# 13_TYPEC0_PROG.net
KiCad netlist of a schematic drawn in Altium Designer
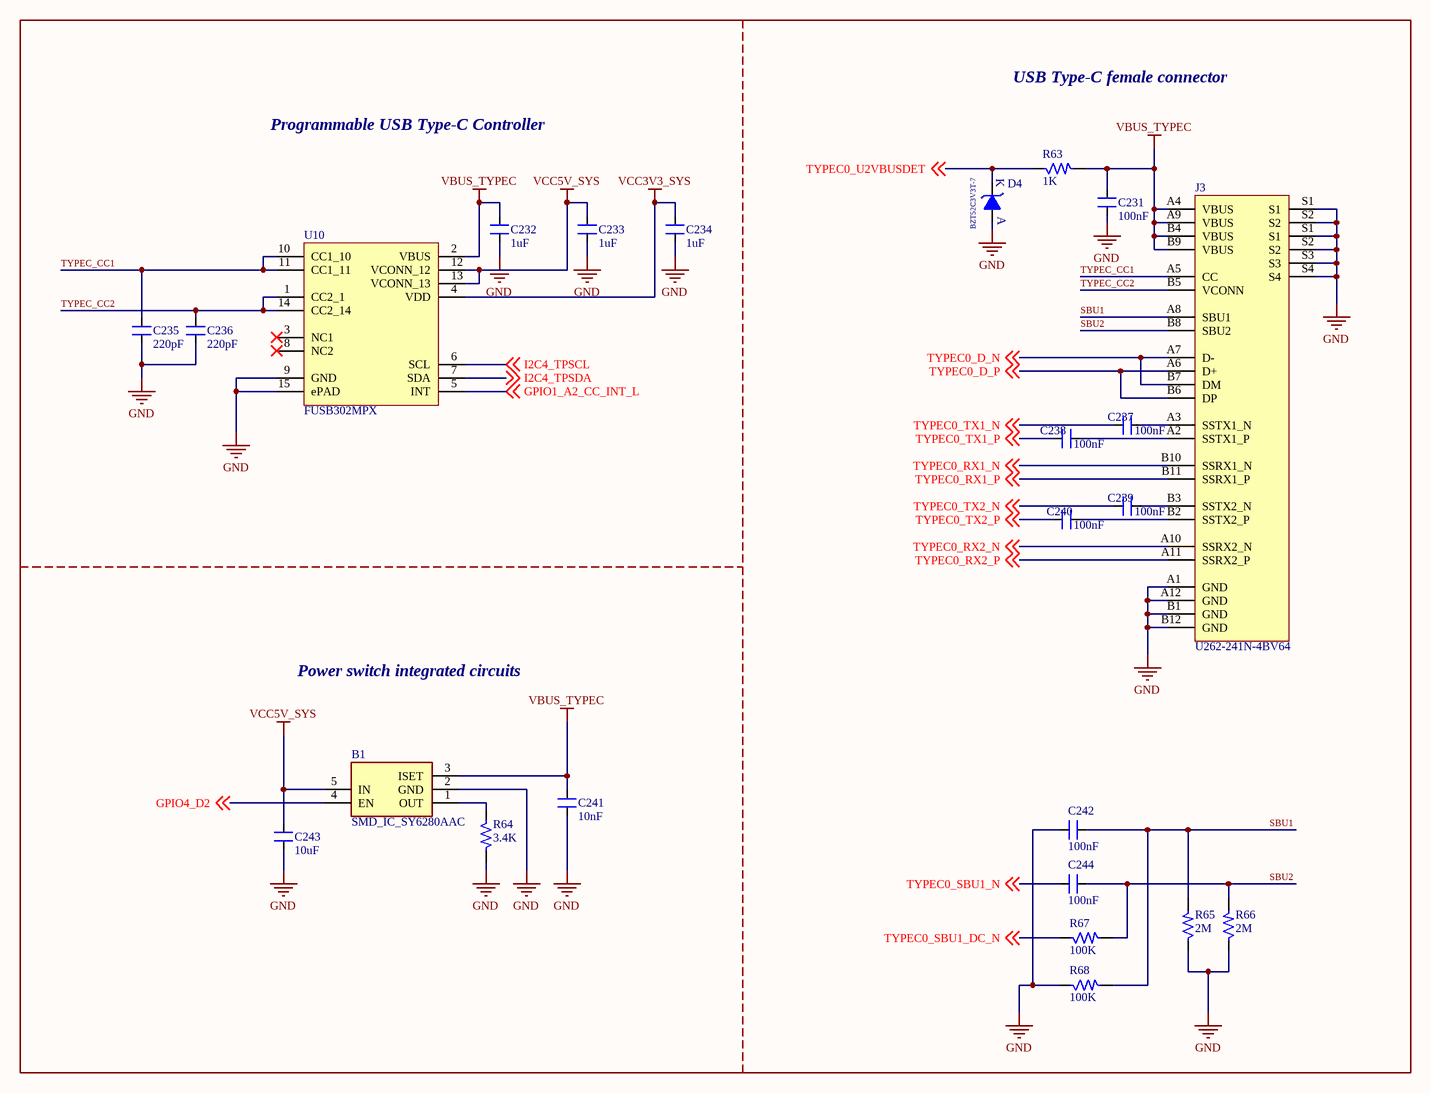
[diagram p0: [13] TYPEC0_PROG.SchDoc]

(export (version "E")
  (design (tool "Eeschema 10.0.6"))
  (components
    (comp (ref "B1")
      (value "SMD_IC_SY6280AAC")
      (footprint "SOT95P285X140-5N")
      (description "Power Switch ICs - Power Distribution")
      (fields
        (field (name "MOUSER PART NUMBER") "909-SMDICSY6280AAC")
        (field (name "MANUFACTURER_PART_NUMBER") "SMD IC SY6280AAC")
      )
      (libsource (lib "SMD_IC_SY6280AAC") (part "SMD_IC_SY6280AAC"))
    )
    (comp (ref "C231")
      (value "100nF")
      (footprint "CAP_0402")
      (description "0.1µF ±10% 25V Ceramic Capacitor X7R 0402 (1005 Metric)")
      (fields
        (field (name "MANUFACTURER") "Walsin Technology Corporation")
        (field (name "MANUFACTURER PART NUMBER") "0402B104K250CT")
      )
      (libsource (lib "EsteemPCB_SOM_Course_intlib") (part "CAP_100nF-25V-10%-0402"))
    )
    (comp (ref "C232")
      (value "1uF")
      (footprint "CAP_0402")
      (description "1µF ±10% 10V Ceramic Capacitor X6S 0402 (1005 Metric)")
      (fields
        (field (name "MANUFACTURER") "Murata Electronics")
        (field (name "MANUFACTURER PART NUMBER") "GRT155C81A105KE01D")
      )
      (libsource (lib "EsteemPCB_SOM_Course_intlib") (part "CAP_1uF-10V-10%-0402"))
    )
    (comp (ref "C233")
      (value "1uF")
      (footprint "CAP_0402")
      (description "1µF ±10% 10V Ceramic Capacitor X6S 0402 (1005 Metric)")
      (fields
        (field (name "MANUFACTURER") "Murata Electronics")
        (field (name "MANUFACTURER PART NUMBER") "GRT155C81A105KE01D")
      )
      (libsource (lib "EsteemPCB_SOM_Course_intlib") (part "CAP_1uF-10V-10%-0402"))
    )
    (comp (ref "C234")
      (value "1uF")
      (footprint "CAP_0402")
      (description "1µF ±10% 10V Ceramic Capacitor X6S 0402 (1005 Metric)")
      (fields
        (field (name "MANUFACTURER") "Murata Electronics")
        (field (name "MANUFACTURER PART NUMBER") "GRT155C81A105KE01D")
      )
      (libsource (lib "EsteemPCB_SOM_Course_intlib") (part "CAP_1uF-10V-10%-0402"))
    )
    (comp (ref "C235")
      (value "220pF")
      (footprint "CAP_0402")
      (description "220pF ±10% 10V Ceramic Capacitor X7R 0402 (1005 Metric)")
      (fields
        (field (name "MANUFACTURER") "KEMET")
        (field (name "MANUFACTURER PART NUMBER") "C0402C221K8RAC7867")
      )
      (libsource (lib "EsteemPCB_SOM_Course_intlib") (part "CAP_220pF-10V-10%-0402"))
    )
    (comp (ref "C236")
      (value "220pF")
      (footprint "CAP_0402")
      (description "220pF ±10% 10V Ceramic Capacitor X7R 0402 (1005 Metric)")
      (fields
        (field (name "MANUFACTURER") "KEMET")
        (field (name "MANUFACTURER PART NUMBER") "C0402C221K8RAC7867")
      )
      (libsource (lib "EsteemPCB_SOM_Course_intlib") (part "CAP_220pF-10V-10%-0402"))
    )
    (comp (ref "C237")
      (value "100nF")
      (footprint "CAP_0201")
      (description "0.1µF ±10% 25V Ceramic Capacitor X5R 0201 (0603 Metric)")
      (fields
        (field (name "MANUFACTURER") "TDK Corporation")
        (field (name "MANUFACTURER PART NUMBER") "C0603X5R1E104K030BB")
      )
      (libsource (lib "EsteemPCB_SOM_Course_intlib") (part "CAP_100nF-25V-10%-0201"))
    )
    (comp (ref "C238")
      (value "100nF")
      (footprint "CAP_0201")
      (description "0.1µF ±10% 25V Ceramic Capacitor X5R 0201 (0603 Metric)")
      (fields
        (field (name "MANUFACTURER") "TDK Corporation")
        (field (name "MANUFACTURER PART NUMBER") "C0603X5R1E104K030BB")
      )
      (libsource (lib "EsteemPCB_SOM_Course_intlib") (part "CAP_100nF-25V-10%-0201"))
    )
    (comp (ref "C239")
      (value "100nF")
      (footprint "CAP_0201")
      (description "0.1µF ±10% 25V Ceramic Capacitor X5R 0201 (0603 Metric)")
      (fields
        (field (name "MANUFACTURER") "TDK Corporation")
        (field (name "MANUFACTURER PART NUMBER") "C0603X5R1E104K030BB")
      )
      (libsource (lib "EsteemPCB_SOM_Course_intlib") (part "CAP_100nF-25V-10%-0201"))
    )
    (comp (ref "C240")
      (value "100nF")
      (footprint "CAP_0201")
      (description "0.1µF ±10% 25V Ceramic Capacitor X5R 0201 (0603 Metric)")
      (fields
        (field (name "MANUFACTURER") "TDK Corporation")
        (field (name "MANUFACTURER PART NUMBER") "C0603X5R1E104K030BB")
      )
      (libsource (lib "EsteemPCB_SOM_Course_intlib") (part "CAP_100nF-25V-10%-0201"))
    )
    (comp (ref "C241")
      (value "10nF")
      (footprint "CAP_0402")
      (description "10000pF ±10% 10V Ceramic Capacitor X7R 0402 (1005 Metric)")
      (fields
        (field (name "MANUFACTURER") "AVX Corporation")
        (field (name "MANUFACTURER PART NUMBER") "0402ZC103KAT2A")
      )
      (libsource (lib "EsteemPCB_SOM_Course_intlib") (part "CAP_10nF-10V-10%-0402"))
    )
    (comp (ref "C242")
      (value "100nF")
      (footprint "CAP_0201")
      (description "0.1µF ±10% 25V Ceramic Capacitor X5R 0201 (0603 Metric)")
      (fields
        (field (name "MANUFACTURER") "TDK Corporation")
        (field (name "MANUFACTURER PART NUMBER") "C0603X5R1E104K030BB")
      )
      (libsource (lib "EsteemPCB_SOM_Course_intlib") (part "CAP_100nF-25V-10%-0201"))
    )
    (comp (ref "C243")
      (value "10uF")
      (footprint "CAP_0402")
      (description "10µF ±20% 10V Ceramic Capacitor X5R 0402 (1005 Metric)")
      (fields
        (field (name "MANUFACTURER PART NUMBER") "CL05A106MP5NUNC")
        (field (name "MANUFACTURER") "Samsung Electro-Mechanics")
      )
      (libsource (lib "EsteemPCB_SOM_Course_intlib") (part "CAP_10uF-10V-20%-0402"))
    )
    (comp (ref "C244")
      (value "100nF")
      (footprint "CAP_0201")
      (description "0.1µF ±10% 25V Ceramic Capacitor X5R 0201 (0603 Metric)")
      (fields
        (field (name "MANUFACTURER") "TDK Corporation")
        (field (name "MANUFACTURER PART NUMBER") "C0603X5R1E104K030BB")
      )
      (libsource (lib "EsteemPCB_SOM_Course_intlib") (part "CAP_100nF-25V-10%-0201"))
    )
    (comp (ref "D4")
      (value "BZT52C3V3T-7")
      (footprint "DIO_SOD523")
      (description "Zener Diode 3.3V 300mW ±6% Surface Mount SOD-523")
      (fields (field (name "MANUFACTURER") "Diodes Incorporated"))
      (libsource (lib "EsteemPCB_SOM_Course_intlib") (part "DIO-Z_3.3V-300mW-SOD-523"))
    )
    (comp (ref "J3")
      (value "U262-241N-4BV64")
      (footprint "CON24_19.64_U262-241N-4BV64_TH_RA")
      (description "USB - Type C Female 24 SMD USB Connectors RoHS")
      (fields (field (name "MANUFACTURER") "XKB Connectivity"))
      (libsource (lib "EsteemPCB_SOM_Course_intlib") (part "CON-TYPEC_U262-241N-4BV64-SMD"))
    )
    (comp (ref "R63")
      (value "1K")
      (footprint "RES_0402")
      (description "1 kOhms ±1% 0.1W, 1/10W Chip Resistor 0402 (1005 Metric) Anti-Sulfur Thin Film")
      (fields
        (field (name "MANUFACTURER") "Vishay Beyschlag/Draloric/BC Components")
        (field (name "MANUFACTURER PART NUMBER") "MCS04020C1001FE000")
      )
      (libsource (lib "EsteemPCB_SOM_Course_intlib") (part "RES_1K-0.1W-1%-0402"))
    )
    (comp (ref "R64")
      (value "3.4K")
      (footprint "RES_0402")
      (description "3.4 kOhms ±1% 0.1W, 1/10W Chip Resistor 0402 (1005 Metric) Automotive AEC-Q200 Thick Film")
      (fields
        (field (name "MANUFACTURER") "Panasonic Electronic Components")
        (field (name "MANUFACTURER PART NUMBER") "ERJ-2RKF3401X")
      )
      (libsource (lib "EsteemPCB_SOM_Course_intlib") (part "RES_3.4K-0.1W-1%-0402"))
    )
    (comp (ref "R65")
      (value "2M")
      (footprint "RES_0201")
      (description "2 MOhms ±1% 0.05W, 1/20W Chip Resistor 0201 (0603 Metric) Thick Film")
      (fields
        (field (name "MANUFACTURER") "Yageo")
        (field (name "MANUFACTURER PART NUMBER") "RC0201FR-072ML")
      )
      (libsource (lib "EsteemPCB_SOM_Course_intlib") (part "RES_2M-0.05W-1%-0201"))
    )
    (comp (ref "R66")
      (value "2M")
      (footprint "RES_0201")
      (description "2 MOhms ±1% 0.05W, 1/20W Chip Resistor 0201 (0603 Metric) Thick Film")
      (fields
        (field (name "MANUFACTURER") "Yageo")
        (field (name "MANUFACTURER PART NUMBER") "RC0201FR-072ML")
      )
      (libsource (lib "EsteemPCB_SOM_Course_intlib") (part "RES_2M-0.05W-1%-0201"))
    )
    (comp (ref "R67")
      (value "100K")
      (footprint "RES_0201")
      (description "100 kOhms ±1% 0.05W, 1/20W Chip Resistor 0201 (0603 Metric) Automotive AEC-Q200 Thick Film")
      (fields
        (field (name "MANUFACTURER") "Panasonic Electronic Components")
        (field (name "MANUFACTURER PART NUMBER") "ERJ-1GNF1003C")
      )
      (libsource (lib "EsteemPCB_SOM_Course_intlib") (part "RES_100K-0.05W-1%-0201"))
    )
    (comp (ref "R68")
      (value "100K")
      (footprint "RES_0201")
      (description "100 kOhms ±1% 0.05W, 1/20W Chip Resistor 0201 (0603 Metric) Automotive AEC-Q200 Thick Film")
      (fields
        (field (name "MANUFACTURER") "Panasonic Electronic Components")
        (field (name "MANUFACTURER PART NUMBER") "ERJ-1GNF1003C")
      )
      (libsource (lib "EsteemPCB_SOM_Course_intlib") (part "RES_100K-0.05W-1%-0201"))
    )
    (comp (ref "U10")
      (value "FUSB302MPX")
      (footprint "MLP-14_98.4X98.4_SMD")
      (description "USB Controller USB 3.1 USB Interface 14-MLP (2.5x2.5)")
      (fields (field (name "MANUFACTURER") "ON Semiconductor"))
      (libsource (lib "EsteemPCB_SOM_Course_intlib") (part "IC_FUSB302MPX"))
    )
  )
  (nets
    (net (code "1") (name "/SBU1") (class "Default")
      (node (ref "C242") (pin "2") (pinfunction "2_2") (pintype "passive"))
      (node (ref "J3") (pin "A8") (pinfunction "SBU1_A8") (pintype "passive"))
      (node (ref "R65") (pin "2") (pinfunction "2_2") (pintype "passive"))
      (node (ref "R68") (pin "2") (pinfunction "2_2") (pintype "passive"))
    )
    (net (code "2") (name "/SBU2") (class "Default")
      (node (ref "C244") (pin "2") (pinfunction "2_2") (pintype "passive"))
      (node (ref "J3") (pin "B8") (pinfunction "SBU2_B8") (pintype "passive"))
      (node (ref "R66") (pin "2") (pinfunction "2_2") (pintype "passive"))
      (node (ref "R67") (pin "2") (pinfunction "2_2") (pintype "passive"))
    )
    (net (code "3") (name "/TYPEC_CC1") (class "Default")
      (node (ref "C235") (pin "2") (pinfunction "2_2") (pintype "passive"))
      (node (ref "J3") (pin "A5") (pinfunction "CC_A5") (pintype "passive"))
      (node (ref "U10") (pin "10") (pinfunction "CC1_10_10") (pintype "passive"))
      (node (ref "U10") (pin "11") (pinfunction "CC1_11_11") (pintype "passive"))
    )
    (net (code "4") (name "/TYPEC_CC2") (class "Default")
      (node (ref "C236") (pin "2") (pinfunction "2_2") (pintype "passive"))
      (node (ref "J3") (pin "B5") (pinfunction "VCONN_B5") (pintype "passive"))
      (node (ref "U10") (pin "1") (pinfunction "CC2_1_1") (pintype "passive"))
      (node (ref "U10") (pin "14") (pinfunction "CC2_14_14") (pintype "passive"))
    )
    (net (code "5") (name "GND") (class "Default")
      (node (ref "B1") (pin "2") (pinfunction "GND_2") (pintype "passive"))
      (node (ref "C231") (pin "1") (pinfunction "1_1") (pintype "passive"))
      (node (ref "C232") (pin "1") (pinfunction "1_1") (pintype "passive"))
      (node (ref "C233") (pin "2") (pinfunction "2_2") (pintype "passive"))
      (node (ref "C234") (pin "1") (pinfunction "1_1") (pintype "passive"))
      (node (ref "C235") (pin "1") (pinfunction "1_1") (pintype "passive"))
      (node (ref "C236") (pin "1") (pinfunction "1_1") (pintype "passive"))
      (node (ref "C241") (pin "1") (pinfunction "1_1") (pintype "passive"))
      (node (ref "C242") (pin "1") (pinfunction "1_1") (pintype "passive"))
      (node (ref "C243") (pin "1") (pinfunction "1_1") (pintype "passive"))
      (node (ref "D4") (pin "A") (pinfunction "A_A") (pintype "passive"))
      (node (ref "J3") (pin "A1") (pinfunction "GND_A1") (pintype "passive"))
      (node (ref "J3") (pin "A12") (pinfunction "GND_A12") (pintype "passive"))
      (node (ref "J3") (pin "B1") (pinfunction "GND_B1") (pintype "passive"))
      (node (ref "J3") (pin "B12") (pinfunction "GND_B12") (pintype "passive"))
      (node (ref "J3") (pin "S1") (pinfunction "S1_S1") (pintype "passive"))
      (node (ref "J3") (pin "S2") (pinfunction "S2_S2") (pintype "passive"))
      (node (ref "J3") (pin "S3") (pinfunction "S3_S3") (pintype "passive"))
      (node (ref "J3") (pin "S4") (pinfunction "S4_S4") (pintype "passive"))
      (node (ref "R64") (pin "2") (pinfunction "2_2") (pintype "passive"))
      (node (ref "R65") (pin "1") (pinfunction "1_1") (pintype "passive"))
      (node (ref "R66") (pin "1") (pinfunction "1_1") (pintype "passive"))
      (node (ref "R68") (pin "1") (pinfunction "1_1") (pintype "passive"))
      (node (ref "U10") (pin "15") (pinfunction "ePAD_15") (pintype "passive"))
      (node (ref "U10") (pin "9") (pinfunction "GND_9") (pintype "passive"))
    )
    (net (code "6") (name "GPIO1_A2_CC_INT_L") (class "Default")
      (node (ref "U10") (pin "5") (pinfunction "INT_5") (pintype "passive"))
    )
    (net (code "7") (name "GPIO4_D2") (class "Default")
      (node (ref "B1") (pin "4") (pinfunction "EN_4") (pintype "passive"))
    )
    (net (code "8") (name "I2C4_TPSCL") (class "Default")
      (node (ref "U10") (pin "6") (pinfunction "SCL_6") (pintype "passive"))
    )
    (net (code "9") (name "I2C4_TPSDA") (class "Default")
      (node (ref "U10") (pin "7") (pinfunction "SDA_7") (pintype "passive"))
    )
    (net (code "10") (name "Net-(B1-OUT)") (class "Default")
      (node (ref "B1") (pin "1") (pinfunction "OUT_1") (pintype "passive"))
      (node (ref "R64") (pin "1") (pinfunction "1_1") (pintype "passive"))
    )
    (net (code "11") (name "Net-(J3-SSTX1_N)") (class "Default")
      (node (ref "C237") (pin "2") (pinfunction "2_2") (pintype "passive"))
      (node (ref "J3") (pin "A3") (pinfunction "SSTX1_N_A3") (pintype "passive"))
    )
    (net (code "12") (name "Net-(J3-SSTX1_P)") (class "Default")
      (node (ref "C238") (pin "2") (pinfunction "2_2") (pintype "passive"))
      (node (ref "J3") (pin "A2") (pinfunction "SSTX1_P_A2") (pintype "passive"))
    )
    (net (code "13") (name "Net-(J3-SSTX2_N)") (class "Default")
      (node (ref "C239") (pin "2") (pinfunction "2_2") (pintype "passive"))
      (node (ref "J3") (pin "B3") (pinfunction "SSTX2_N_B3") (pintype "passive"))
    )
    (net (code "14") (name "Net-(J3-SSTX2_P)") (class "Default")
      (node (ref "C240") (pin "2") (pinfunction "2_2") (pintype "passive"))
      (node (ref "J3") (pin "B2") (pinfunction "SSTX2_P_B2") (pintype "passive"))
    )
    (net (code "15") (name "TYPEC0_D_N") (class "Default")
      (node (ref "J3") (pin "A7") (pinfunction "D-_A7") (pintype "passive"))
      (node (ref "J3") (pin "B7") (pinfunction "DM_B7") (pintype "passive"))
    )
    (net (code "16") (name "TYPEC0_D_P") (class "Default")
      (node (ref "J3") (pin "A6") (pinfunction "D+_A6") (pintype "passive"))
      (node (ref "J3") (pin "B6") (pinfunction "DP_B6") (pintype "passive"))
    )
    (net (code "17") (name "TYPEC0_RX1_N") (class "Default")
      (node (ref "J3") (pin "B10") (pinfunction "SSRX1_N_B10") (pintype "passive"))
    )
    (net (code "18") (name "TYPEC0_RX1_P") (class "Default")
      (node (ref "J3") (pin "B11") (pinfunction "SSRX1_P_B11") (pintype "passive"))
    )
    (net (code "19") (name "TYPEC0_RX2_N") (class "Default")
      (node (ref "J3") (pin "A10") (pinfunction "SSRX2_N_A10") (pintype "passive"))
    )
    (net (code "20") (name "TYPEC0_RX2_P") (class "Default")
      (node (ref "J3") (pin "A11") (pinfunction "SSRX2_P_A11") (pintype "passive"))
    )
    (net (code "21") (name "TYPEC0_SBU1_DC_N") (class "Default")
      (node (ref "R67") (pin "1") (pinfunction "1_1") (pintype "passive"))
    )
    (net (code "22") (name "TYPEC0_SBU1_N") (class "Default")
      (node (ref "C244") (pin "1") (pinfunction "1_1") (pintype "passive"))
    )
    (net (code "23") (name "TYPEC0_TX1_N") (class "Default")
      (node (ref "C237") (pin "1") (pinfunction "1_1") (pintype "passive"))
    )
    (net (code "24") (name "TYPEC0_TX1_P") (class "Default")
      (node (ref "C238") (pin "1") (pinfunction "1_1") (pintype "passive"))
    )
    (net (code "25") (name "TYPEC0_TX2_N") (class "Default")
      (node (ref "C239") (pin "1") (pinfunction "1_1") (pintype "passive"))
    )
    (net (code "26") (name "TYPEC0_TX2_P") (class "Default")
      (node (ref "C240") (pin "1") (pinfunction "1_1") (pintype "passive"))
    )
    (net (code "27") (name "TYPEC0_U2VBUSDET") (class "Default")
      (node (ref "D4") (pin "K") (pinfunction "K_K") (pintype "passive"))
      (node (ref "R63") (pin "1") (pinfunction "1_1") (pintype "passive"))
    )
    (net (code "28") (name "VBUS_TYPEC") (class "Default")
      (node (ref "B1") (pin "3") (pinfunction "ISET_3") (pintype "passive"))
      (node (ref "C231") (pin "2") (pinfunction "2_2") (pintype "passive"))
      (node (ref "C232") (pin "2") (pinfunction "2_2") (pintype "passive"))
      (node (ref "C241") (pin "2") (pinfunction "2_2") (pintype "passive"))
      (node (ref "J3") (pin "A4") (pinfunction "VBUS_A4") (pintype "passive"))
      (node (ref "J3") (pin "A9") (pinfunction "VBUS_A9") (pintype "passive"))
      (node (ref "J3") (pin "B4") (pinfunction "VBUS_B4") (pintype "passive"))
      (node (ref "J3") (pin "B9") (pinfunction "VBUS_B9") (pintype "passive"))
      (node (ref "R63") (pin "2") (pinfunction "2_2") (pintype "passive"))
      (node (ref "U10") (pin "2") (pinfunction "VBUS_2") (pintype "passive"))
    )
    (net (code "29") (name "VCC3V3_SYS") (class "Default")
      (node (ref "C234") (pin "2") (pinfunction "2_2") (pintype "passive"))
      (node (ref "U10") (pin "4") (pinfunction "VDD_4") (pintype "passive"))
    )
    (net (code "30") (name "VCC5V_SYS") (class "Default")
      (node (ref "B1") (pin "5") (pinfunction "IN_5") (pintype "passive"))
      (node (ref "C233") (pin "1") (pinfunction "1_1") (pintype "passive"))
      (node (ref "C243") (pin "2") (pinfunction "2_2") (pintype "passive"))
      (node (ref "U10") (pin "12") (pinfunction "VCONN_12_12") (pintype "passive"))
      (node (ref "U10") (pin "13") (pinfunction "VCONN_13_13") (pintype "passive"))
    )
    (net (code "31") (name "unconnected-(U10-NC1-Pad3)") (class "Default")
      (node (ref "U10") (pin "3") (pinfunction "NC1_3") (pintype "passive+no_connect"))
    )
    (net (code "32") (name "unconnected-(U10-NC2-Pad8)") (class "Default")
      (node (ref "U10") (pin "8") (pinfunction "NC2_8") (pintype "passive+no_connect"))
    )
  )
)
